# botonera.net
KiCad netlist of a schematic drawn in Altium Designer
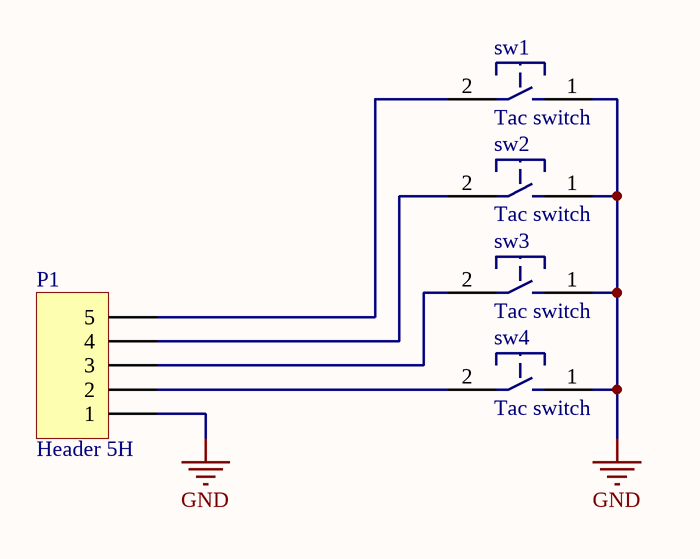
[diagram p0: botonera.SchDoc]

(export (version "E")
  (design (tool "Eeschema 10.0.6"))
  (components
    (comp (ref "P1")
      (value "Header 5H")
      (footprint "HDR1X5H")
      (description "Header, 5-Pin, Right Angle")
      (fields (field (name "PUBLISHER") "Altium Limited"))
      (libsource (lib "Miscellaneous Connectors") (part "Header 5H"))
    )
    (comp (ref "sw1")
      (value "Tac switch")
      (footprint "MY_TACTILE-PTH")
      (description "small tac switch")
      (libsource (lib "Mylib") (part "Tac switch"))
    )
    (comp (ref "sw2")
      (value "Tac switch")
      (footprint "MY_TACTILE-PTH")
      (description "small tac switch")
      (libsource (lib "Mylib") (part "Tac switch"))
    )
    (comp (ref "sw3")
      (value "Tac switch")
      (footprint "MY_TACTILE-PTH")
      (description "small tac switch")
      (libsource (lib "Mylib") (part "Tac switch"))
    )
    (comp (ref "sw4")
      (value "Tac switch")
      (footprint "MY_TACTILE-PTH")
      (description "small tac switch")
      (libsource (lib "Mylib") (part "Tac switch"))
    )
  )
  (nets
    (net (code "1") (name "GND") (class "Default")
      (node (ref "P1") (pin "1") (pinfunction "1_1") (pintype "passive"))
      (node (ref "sw1") (pin "1") (pinfunction "1_1") (pintype "passive"))
      (node (ref "sw2") (pin "1") (pinfunction "1_1") (pintype "passive"))
      (node (ref "sw3") (pin "1") (pinfunction "1_1") (pintype "passive"))
      (node (ref "sw4") (pin "1") (pinfunction "1_1") (pintype "passive"))
    )
    (net (code "2") (name "Net-(P1-Pad2)") (class "Default")
      (node (ref "P1") (pin "2") (pinfunction "2_2") (pintype "passive"))
      (node (ref "sw4") (pin "2") (pinfunction "2_2") (pintype "passive"))
    )
    (net (code "3") (name "Net-(P1-Pad3)") (class "Default")
      (node (ref "P1") (pin "3") (pinfunction "3_3") (pintype "passive"))
      (node (ref "sw3") (pin "2") (pinfunction "2_2") (pintype "passive"))
    )
    (net (code "4") (name "Net-(P1-Pad4)") (class "Default")
      (node (ref "P1") (pin "4") (pinfunction "4_4") (pintype "passive"))
      (node (ref "sw2") (pin "2") (pinfunction "2_2") (pintype "passive"))
    )
    (net (code "5") (name "Net-(P1-Pad5)") (class "Default")
      (node (ref "P1") (pin "5") (pinfunction "5_5") (pintype "passive"))
      (node (ref "sw1") (pin "2") (pinfunction "2_2") (pintype "passive"))
    )
  )
)
